# 5_-Motor_Driver_Schematic.net
KiCad netlist of a schematic drawn in Altium Designer
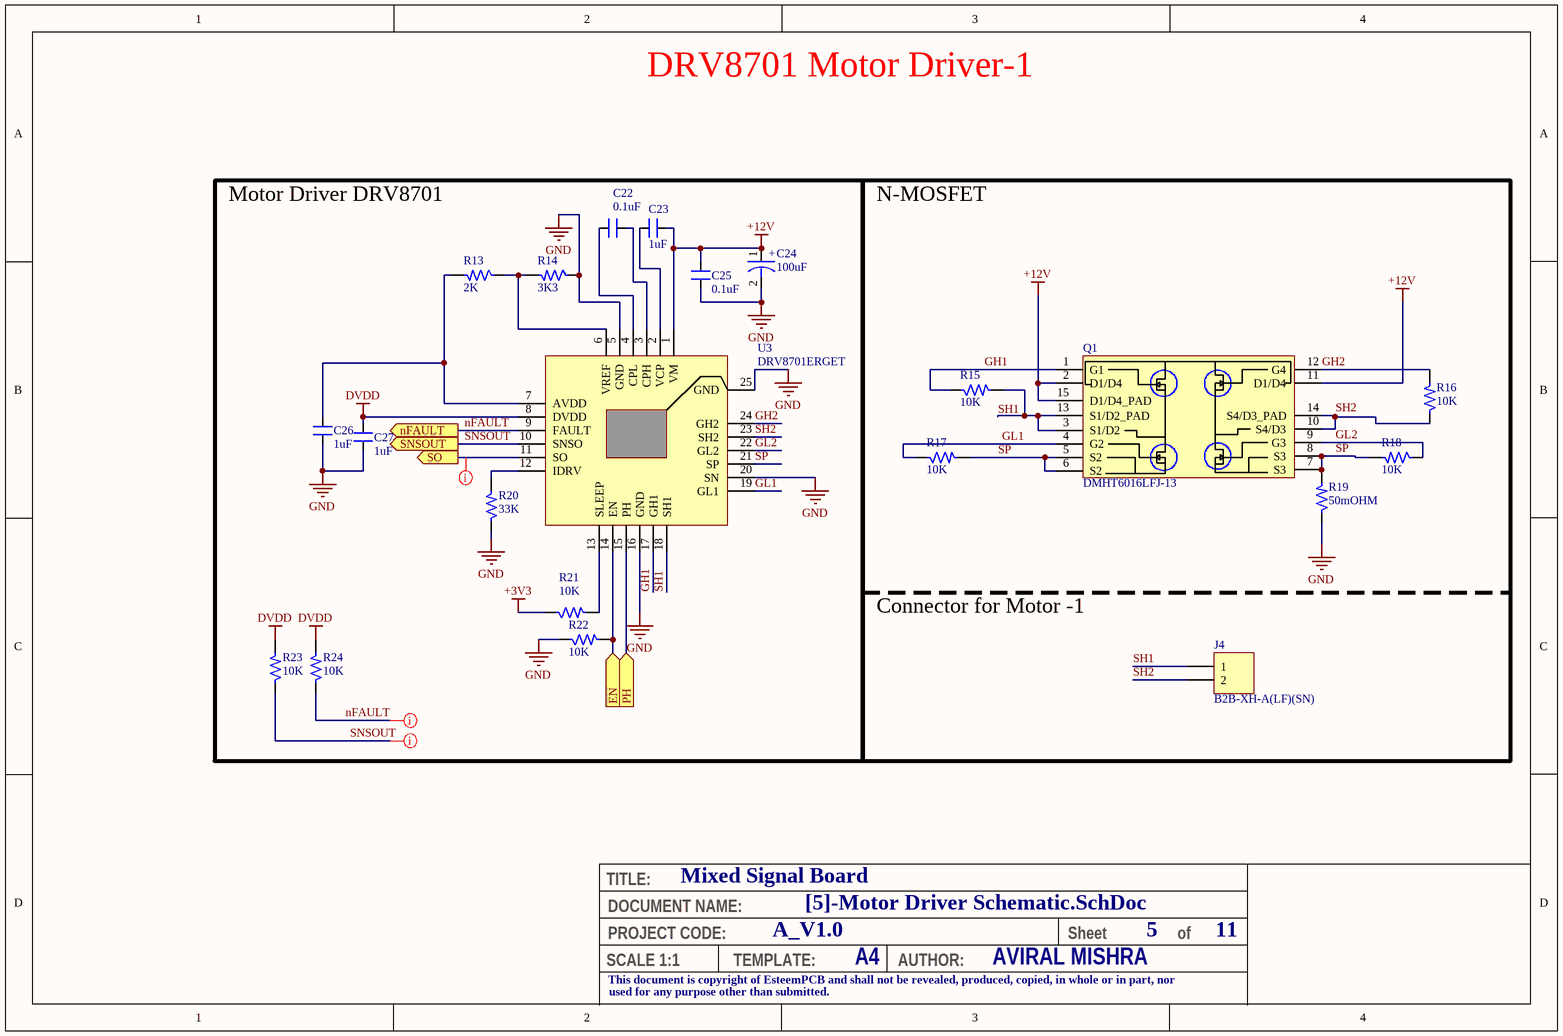
[diagram p0: [5]-Motor Driver Schematic.SchDoc]

(export (version "E")
  (design (tool "Eeschema 10.0.6"))
  (components
    (comp (ref "C22")
      (value "0.1uF")
      (footprint "CAP_0805")
      (description "0.1µF ±10% 50V Ceramic Capacitor X7R 0805 (2012 Metric)")
      (fields
        (field (name "MANUFACTURER") "Samsung")
        (field (name "MANUFACTURER PART NUMBER") "CL21B104KBCNNNC")
      )
      (libsource (lib "ESTEEMPCBLIB") (part "CAP_0.1uF-50V-10%-0805"))
    )
    (comp (ref "C23")
      (value "1uF")
      (footprint "CAP_0805")
      (description "1µF ±5% 50V Ceramic Capacitor X7R 0805 (2012 Metric)")
      (fields
        (field (name "MANUFACTURER") "Samsung")
        (field (name "MANUFACTURER PART NUMBER") "CC0805JKX7R9BB105")
      )
      (libsource (lib "ESTEEMPCBLIB") (part "CAP_1uF-50V-5%-0805"))
    )
    (comp (ref "C24")
      (value "100uF")
      (footprint "ACAP_P236_D305_H303_RAD")
      (description "100µF 25V Aluminum Electrolytic Capacitors Radial, Can - SMD 1000 Hrs @ 105°C")
      (fields
        (field (name "MANUFACTURER") "Nichicon")
        (field (name "MANUFACTURER PART NUMBER") "UWT1E101MCL1GS")
      )
      (libsource (lib "ESTEEMPCBLIB") (part "CAP-P_100uF-25V-20%-RAD"))
    )
    (comp (ref "C25")
      (value "0.1uF")
      (footprint "CAP_0805")
      (description "0.1µF ±10% 50V Ceramic Capacitor X7R 0805 (2012 Metric)")
      (fields
        (field (name "MANUFACTURER") "Samsung")
        (field (name "MANUFACTURER PART NUMBER") "CL21B104KBCNNNC")
      )
      (libsource (lib "ESTEEMPCBLIB") (part "CAP_0.1uF-50V-10%-0805"))
    )
    (comp (ref "C26")
      (value "1uF")
      (footprint "CAP_0805")
      (description "1µF ±5% 50V Ceramic Capacitor X7R 0805 (2012 Metric)")
      (fields
        (field (name "MANUFACTURER") "Samsung")
        (field (name "MANUFACTURER PART NUMBER") "CC0805JKX7R9BB105")
      )
      (libsource (lib "ESTEEMPCBLIB") (part "CAP_1uF-50V-5%-0805"))
    )
    (comp (ref "C27")
      (value "1uF")
      (footprint "CAP_0805")
      (description "1µF ±5% 50V Ceramic Capacitor X7R 0805 (2012 Metric)")
      (fields
        (field (name "MANUFACTURER") "Samsung")
        (field (name "MANUFACTURER PART NUMBER") "CC0805JKX7R9BB105")
      )
      (libsource (lib "ESTEEMPCBLIB") (part "CAP_1uF-50V-5%-0805"))
    )
    (comp (ref "J4")
      (value "B2B-XH-A(LF)(SN)")
      (footprint "CON2_100_B2B-XH-A_TH_ST")
      (description "2 Pins, 1 Row 2.54mm Pitch, Straight Connector, male")
      (fields (field (name "MANUFACTURER") "JST") (field (name "MATING PART NUMBER") "XHP-2"))
      (libsource (lib "ESTEEMPCBLIB") (part "CON-PLG_2X1-100-ST-TH"))
    )
    (comp (ref "Q1")
      (value "DMHT6016LFJ-13")
      (footprint "DFN5045-12_33_212_27X15_SMD_1")
      (description "Mosfet Array 4 N-Channel 14.8A (Ta) Surface Mount V-DFN5045-12")
      (fields (field (name "MANUFACTURER") "ON Semiconductor"))
      (libsource (lib "ESTEEMPCBLIB") (part "MOSFET-N_60V-14.8A-V-DFN5045-12"))
    )
    (comp (ref "R13")
      (value "2K")
      (footprint "RES_0603")
      (fields
        (field (name "MANUFACTURER") "Stackpole Electronics")
        (field (name "MANUFACTURER PART NUMBER") "RNCP0603FTD2K00")
      )
      (libsource (lib "ESTEEMPCBLIB") (part "RES_2K-0.125W-1%-0603"))
    )
    (comp (ref "R14")
      (value "3K3")
      (footprint "RES_0603")
      (description "3.3 kOhms ±1% 0.1W, 1/10W Chip Resistor 0603 (1608 Metric) Automotive AEC-Q200 Thick Film")
      (fields (field (name "MANUFACTURER") "Wilson") (field (name "MANUFACTURER PART NUMBER") "WR06X3301FTL"))
      (libsource (lib "ESTEEMPCBLIB") (part "RES_3.3K-0.1W-1%-0603"))
    )
    (comp (ref "R15")
      (value "10K")
      (footprint "RES_0603")
      (description "10 kOhms ±1% 0.1W, 1/10W Chip Resistor 0603 (1608 Metric) Automotive AEC-Q200 Thick Film")
      (fields (field (name "MANUFACTURER") "Walsin") (field (name "MANUFACTURER PART NUMBER") "WR06X1002FTL"))
      (libsource (lib "ESTEEMPCBLIB") (part "RES_10K-0.1W-1%-0603"))
    )
    (comp (ref "R16")
      (value "10K")
      (footprint "RES_0603")
      (description "10 kOhms ±1% 0.1W, 1/10W Chip Resistor 0603 (1608 Metric) Automotive AEC-Q200 Thick Film")
      (fields (field (name "MANUFACTURER") "Walsin") (field (name "MANUFACTURER PART NUMBER") "WR06X1002FTL"))
      (libsource (lib "ESTEEMPCBLIB") (part "RES_10K-0.1W-1%-0603"))
    )
    (comp (ref "R17")
      (value "10K")
      (footprint "RES_0603")
      (description "10 kOhms ±1% 0.1W, 1/10W Chip Resistor 0603 (1608 Metric) Automotive AEC-Q200 Thick Film")
      (fields (field (name "MANUFACTURER") "Walsin") (field (name "MANUFACTURER PART NUMBER") "WR06X1002FTL"))
      (libsource (lib "ESTEEMPCBLIB") (part "RES_10K-0.1W-1%-0603"))
    )
    (comp (ref "R18")
      (value "10K")
      (footprint "RES_0603")
      (description "10 kOhms ±1% 0.1W, 1/10W Chip Resistor 0603 (1608 Metric) Automotive AEC-Q200 Thick Film")
      (fields (field (name "MANUFACTURER") "Walsin") (field (name "MANUFACTURER PART NUMBER") "WR06X1002FTL"))
      (libsource (lib "ESTEEMPCBLIB") (part "RES_10K-0.1W-1%-0603"))
    )
    (comp (ref "R19")
      (value "50mOHM")
      (footprint "RES_2512")
      (fields
        (field (name "MANUFACTURER") "Yageo")
        (field (name "MANUFACTURER PART NUMBER") "PA2512FKF7W0R05E")
      )
      (libsource (lib "ESTEEMPCBLIB") (part "RES_50mOhm-2W-1%-2512"))
    )
    (comp (ref "R20")
      (value "33K")
      (footprint "RES_0805")
      (fields
        (field (name "MANUFACTURER") "Vishay BCcomponents")
        (field (name "MANUFACTURER PART NUMBER") "CRG0805F33K")
      )
      (libsource (lib "ESTEEMPCBLIB") (part "RES_33K-0.125W-1%-0805"))
    )
    (comp (ref "R21")
      (value "10K")
      (footprint "RES_0603")
      (description "10 kOhms ±1% 0.1W, 1/10W Chip Resistor 0603 (1608 Metric) Automotive AEC-Q200 Thick Film")
      (fields (field (name "MANUFACTURER") "Walsin") (field (name "MANUFACTURER PART NUMBER") "WR06X1002FTL"))
      (libsource (lib "ESTEEMPCBLIB") (part "RES_10K-0.1W-1%-0603"))
    )
    (comp (ref "R22")
      (value "10K")
      (footprint "RES_0603")
      (description "10 kOhms ±1% 0.1W, 1/10W Chip Resistor 0603 (1608 Metric) Automotive AEC-Q200 Thick Film")
      (fields (field (name "MANUFACTURER") "Walsin") (field (name "MANUFACTURER PART NUMBER") "WR06X1002FTL"))
      (libsource (lib "ESTEEMPCBLIB") (part "RES_10K-0.1W-1%-0603"))
    )
    (comp (ref "R23")
      (value "10K")
      (footprint "RES_0603")
      (description "10 kOhms ±1% 0.1W, 1/10W Chip Resistor 0603 (1608 Metric) Automotive AEC-Q200 Thick Film")
      (fields (field (name "MANUFACTURER") "Walsin") (field (name "MANUFACTURER PART NUMBER") "WR06X1002FTL"))
      (libsource (lib "ESTEEMPCBLIB") (part "RES_10K-0.1W-1%-0603"))
    )
    (comp (ref "R24")
      (value "10K")
      (footprint "RES_0603")
      (description "10 kOhms ±1% 0.1W, 1/10W Chip Resistor 0603 (1608 Metric) Automotive AEC-Q200 Thick Film")
      (fields (field (name "MANUFACTURER") "Walsin") (field (name "MANUFACTURER PART NUMBER") "WR06X1002FTL"))
      (libsource (lib "ESTEEMPCBLIB") (part "RES_10K-0.1W-1%-0603"))
    )
    (comp (ref "U3")
      (value "DRV8701ERGET")
      (footprint "VFQFN24_19.6_196_12X32_SMD_1")
      (description "Motor Driver Power MOSFET Parallel 24-VQFN (4x4)")
      (fields (field (name "MANUFACTURER") "Texas Instruments"))
      (libsource (lib "ESTEEMPCBLIB") (part "IC_DRV8701ERGET"))
    )
  )
  (nets
    (net (code "1") (name "+3V3") (class "Default")
      (node (ref "R21") (pin "1") (pinfunction "1_1") (pintype "passive"))
    )
    (net (code "2") (name "+12V") (class "Default")
      (node (ref "C23") (pin "2") (pinfunction "2_2") (pintype "passive"))
      (node (ref "C24") (pin "1") (pinfunction "1_1") (pintype "passive"))
      (node (ref "C25") (pin "2") (pinfunction "2_2") (pintype "passive"))
      (node (ref "Q1") (pin "11") (pinfunction "D1/D4_11") (pintype "passive"))
      (node (ref "Q1") (pin "15") (pinfunction "D1/D4_PAD_15") (pintype "passive"))
      (node (ref "Q1") (pin "2") (pinfunction "D1/D4_2") (pintype "passive"))
      (node (ref "U3") (pin "1") (pinfunction "VM_1") (pintype "passive"))
    )
    (net (code "3") (name "/EN") (class "Default")
      (node (ref "R22") (pin "2") (pinfunction "2_2") (pintype "passive"))
      (node (ref "U3") (pin "14") (pinfunction "EN_14") (pintype "passive"))
    )
    (net (code "4") (name "/GH1") (class "Default")
      (node (ref "Q1") (pin "1") (pinfunction "G1_1") (pintype "passive"))
      (node (ref "R15") (pin "1") (pinfunction "1_1") (pintype "passive"))
      (node (ref "U3") (pin "17") (pinfunction "GH1_17") (pintype "passive"))
    )
    (net (code "5") (name "/GH2") (class "Default")
      (node (ref "Q1") (pin "12") (pinfunction "G4_12") (pintype "passive"))
      (node (ref "R16") (pin "2") (pinfunction "2_2") (pintype "passive"))
      (node (ref "U3") (pin "24") (pinfunction "GH2_24") (pintype "passive"))
    )
    (net (code "6") (name "/GL1") (class "Default")
      (node (ref "Q1") (pin "4") (pinfunction "G2_4") (pintype "passive"))
      (node (ref "R17") (pin "1") (pinfunction "1_1") (pintype "passive"))
      (node (ref "U3") (pin "19") (pinfunction "GL1_19") (pintype "passive"))
    )
    (net (code "7") (name "/GL2") (class "Default")
      (node (ref "Q1") (pin "9") (pinfunction "G3_9") (pintype "passive"))
      (node (ref "R18") (pin "1") (pinfunction "1_1") (pintype "passive"))
      (node (ref "U3") (pin "22") (pinfunction "GL2_22") (pintype "passive"))
    )
    (net (code "8") (name "/PH") (class "Default")
      (node (ref "U3") (pin "15") (pinfunction "PH_15") (pintype "passive"))
    )
    (net (code "9") (name "/SH1") (class "Default")
      (node (ref "J4") (pin "1") (pinfunction "1_1") (pintype "passive"))
      (node (ref "Q1") (pin "13") (pinfunction "S1/D2_PAD_13") (pintype "passive"))
      (node (ref "Q1") (pin "3") (pinfunction "S1/D2_3") (pintype "passive"))
      (node (ref "R15") (pin "2") (pinfunction "2_2") (pintype "passive"))
      (node (ref "U3") (pin "18") (pinfunction "SH1_18") (pintype "passive"))
    )
    (net (code "10") (name "/SH2") (class "Default")
      (node (ref "J4") (pin "2") (pinfunction "2_2") (pintype "passive"))
      (node (ref "Q1") (pin "10") (pinfunction "S4/D3_10") (pintype "passive"))
      (node (ref "Q1") (pin "14") (pinfunction "S4/D3_PAD_14") (pintype "passive"))
      (node (ref "R16") (pin "1") (pinfunction "1_1") (pintype "passive"))
      (node (ref "U3") (pin "23") (pinfunction "SH2_23") (pintype "passive"))
    )
    (net (code "11") (name "/SNSOUT") (class "Default")
      (node (ref "R23") (pin "1") (pinfunction "1_1") (pintype "passive"))
      (node (ref "U3") (pin "10") (pinfunction "SNSO_10") (pintype "passive"))
    )
    (net (code "12") (name "/SO") (class "Default")
      (node (ref "U3") (pin "11") (pinfunction "SO_11") (pintype "passive"))
    )
    (net (code "13") (name "/SP") (class "Default")
      (node (ref "Q1") (pin "5") (pinfunction "S2_5") (pintype "passive"))
      (node (ref "Q1") (pin "6") (pinfunction "S2_6") (pintype "passive"))
      (node (ref "Q1") (pin "7") (pinfunction "S3_7") (pintype "passive"))
      (node (ref "Q1") (pin "8") (pinfunction "S3_8") (pintype "passive"))
      (node (ref "R17") (pin "2") (pinfunction "2_2") (pintype "passive"))
      (node (ref "R18") (pin "2") (pinfunction "2_2") (pintype "passive"))
      (node (ref "R19") (pin "2") (pinfunction "2_2") (pintype "passive"))
      (node (ref "U3") (pin "21") (pinfunction "SP_21") (pintype "passive"))
    )
    (net (code "14") (name "/nFAULT") (class "Default")
      (node (ref "R24") (pin "1") (pinfunction "1_1") (pintype "passive"))
      (node (ref "U3") (pin "9") (pinfunction "FAULT_9") (pintype "passive"))
    )
    (net (code "15") (name "DVDD") (class "Default")
      (node (ref "C27") (pin "2") (pinfunction "2_2") (pintype "passive"))
      (node (ref "R23") (pin "2") (pinfunction "2_2") (pintype "passive"))
      (node (ref "R24") (pin "2") (pinfunction "2_2") (pintype "passive"))
      (node (ref "U3") (pin "8") (pinfunction "DVDD_8") (pintype "passive"))
    )
    (net (code "16") (name "GND") (class "Default")
      (node (ref "C24") (pin "2") (pinfunction "2_2") (pintype "passive"))
      (node (ref "C25") (pin "1") (pinfunction "1_1") (pintype "passive"))
      (node (ref "C26") (pin "1") (pinfunction "1_1") (pintype "passive"))
      (node (ref "C27") (pin "1") (pinfunction "1_1") (pintype "passive"))
      (node (ref "R14") (pin "1") (pinfunction "1_1") (pintype "passive"))
      (node (ref "R19") (pin "1") (pinfunction "1_1") (pintype "passive"))
      (node (ref "R20") (pin "1") (pinfunction "1_1") (pintype "passive"))
      (node (ref "R22") (pin "1") (pinfunction "1_1") (pintype "passive"))
      (node (ref "U3") (pin "16") (pinfunction "GND_16") (pintype "passive"))
      (node (ref "U3") (pin "20") (pinfunction "SN_20") (pintype "passive"))
      (node (ref "U3") (pin "25") (pinfunction "GND_25") (pintype "passive"))
      (node (ref "U3") (pin "5") (pinfunction "GND_5") (pintype "passive"))
    )
    (net (code "17") (name "Net-(U3-AVDD)") (class "Default")
      (node (ref "C26") (pin "2") (pinfunction "2_2") (pintype "passive"))
      (node (ref "R13") (pin "2") (pinfunction "2_2") (pintype "passive"))
      (node (ref "U3") (pin "7") (pinfunction "AVDD_7") (pintype "passive"))
    )
    (net (code "18") (name "Net-(U3-CPH)") (class "Default")
      (node (ref "C22") (pin "1") (pinfunction "1_1") (pintype "passive"))
      (node (ref "U3") (pin "3") (pinfunction "CPH_3") (pintype "passive"))
    )
    (net (code "19") (name "Net-(U3-CPL)") (class "Default")
      (node (ref "C22") (pin "2") (pinfunction "2_2") (pintype "passive"))
      (node (ref "U3") (pin "4") (pinfunction "CPL_4") (pintype "passive"))
    )
    (net (code "20") (name "Net-(U3-IDRV)") (class "Default")
      (node (ref "R20") (pin "2") (pinfunction "2_2") (pintype "passive"))
      (node (ref "U3") (pin "12") (pinfunction "IDRV_12") (pintype "passive"))
    )
    (net (code "21") (name "Net-(U3-SLEEP)") (class "Default")
      (node (ref "R21") (pin "2") (pinfunction "2_2") (pintype "passive"))
      (node (ref "U3") (pin "13") (pinfunction "SLEEP_13") (pintype "passive"))
    )
    (net (code "22") (name "Net-(U3-VCP)") (class "Default")
      (node (ref "C23") (pin "1") (pinfunction "1_1") (pintype "passive"))
      (node (ref "U3") (pin "2") (pinfunction "VCP_2") (pintype "passive"))
    )
    (net (code "23") (name "Net-(U3-VREF)") (class "Default")
      (node (ref "R13") (pin "1") (pinfunction "1_1") (pintype "passive"))
      (node (ref "R14") (pin "2") (pinfunction "2_2") (pintype "passive"))
      (node (ref "U3") (pin "6") (pinfunction "VREF_6") (pintype "passive"))
    )
  )
)
